# 4.net
KiCad netlist of a schematic drawn in Altium Designer
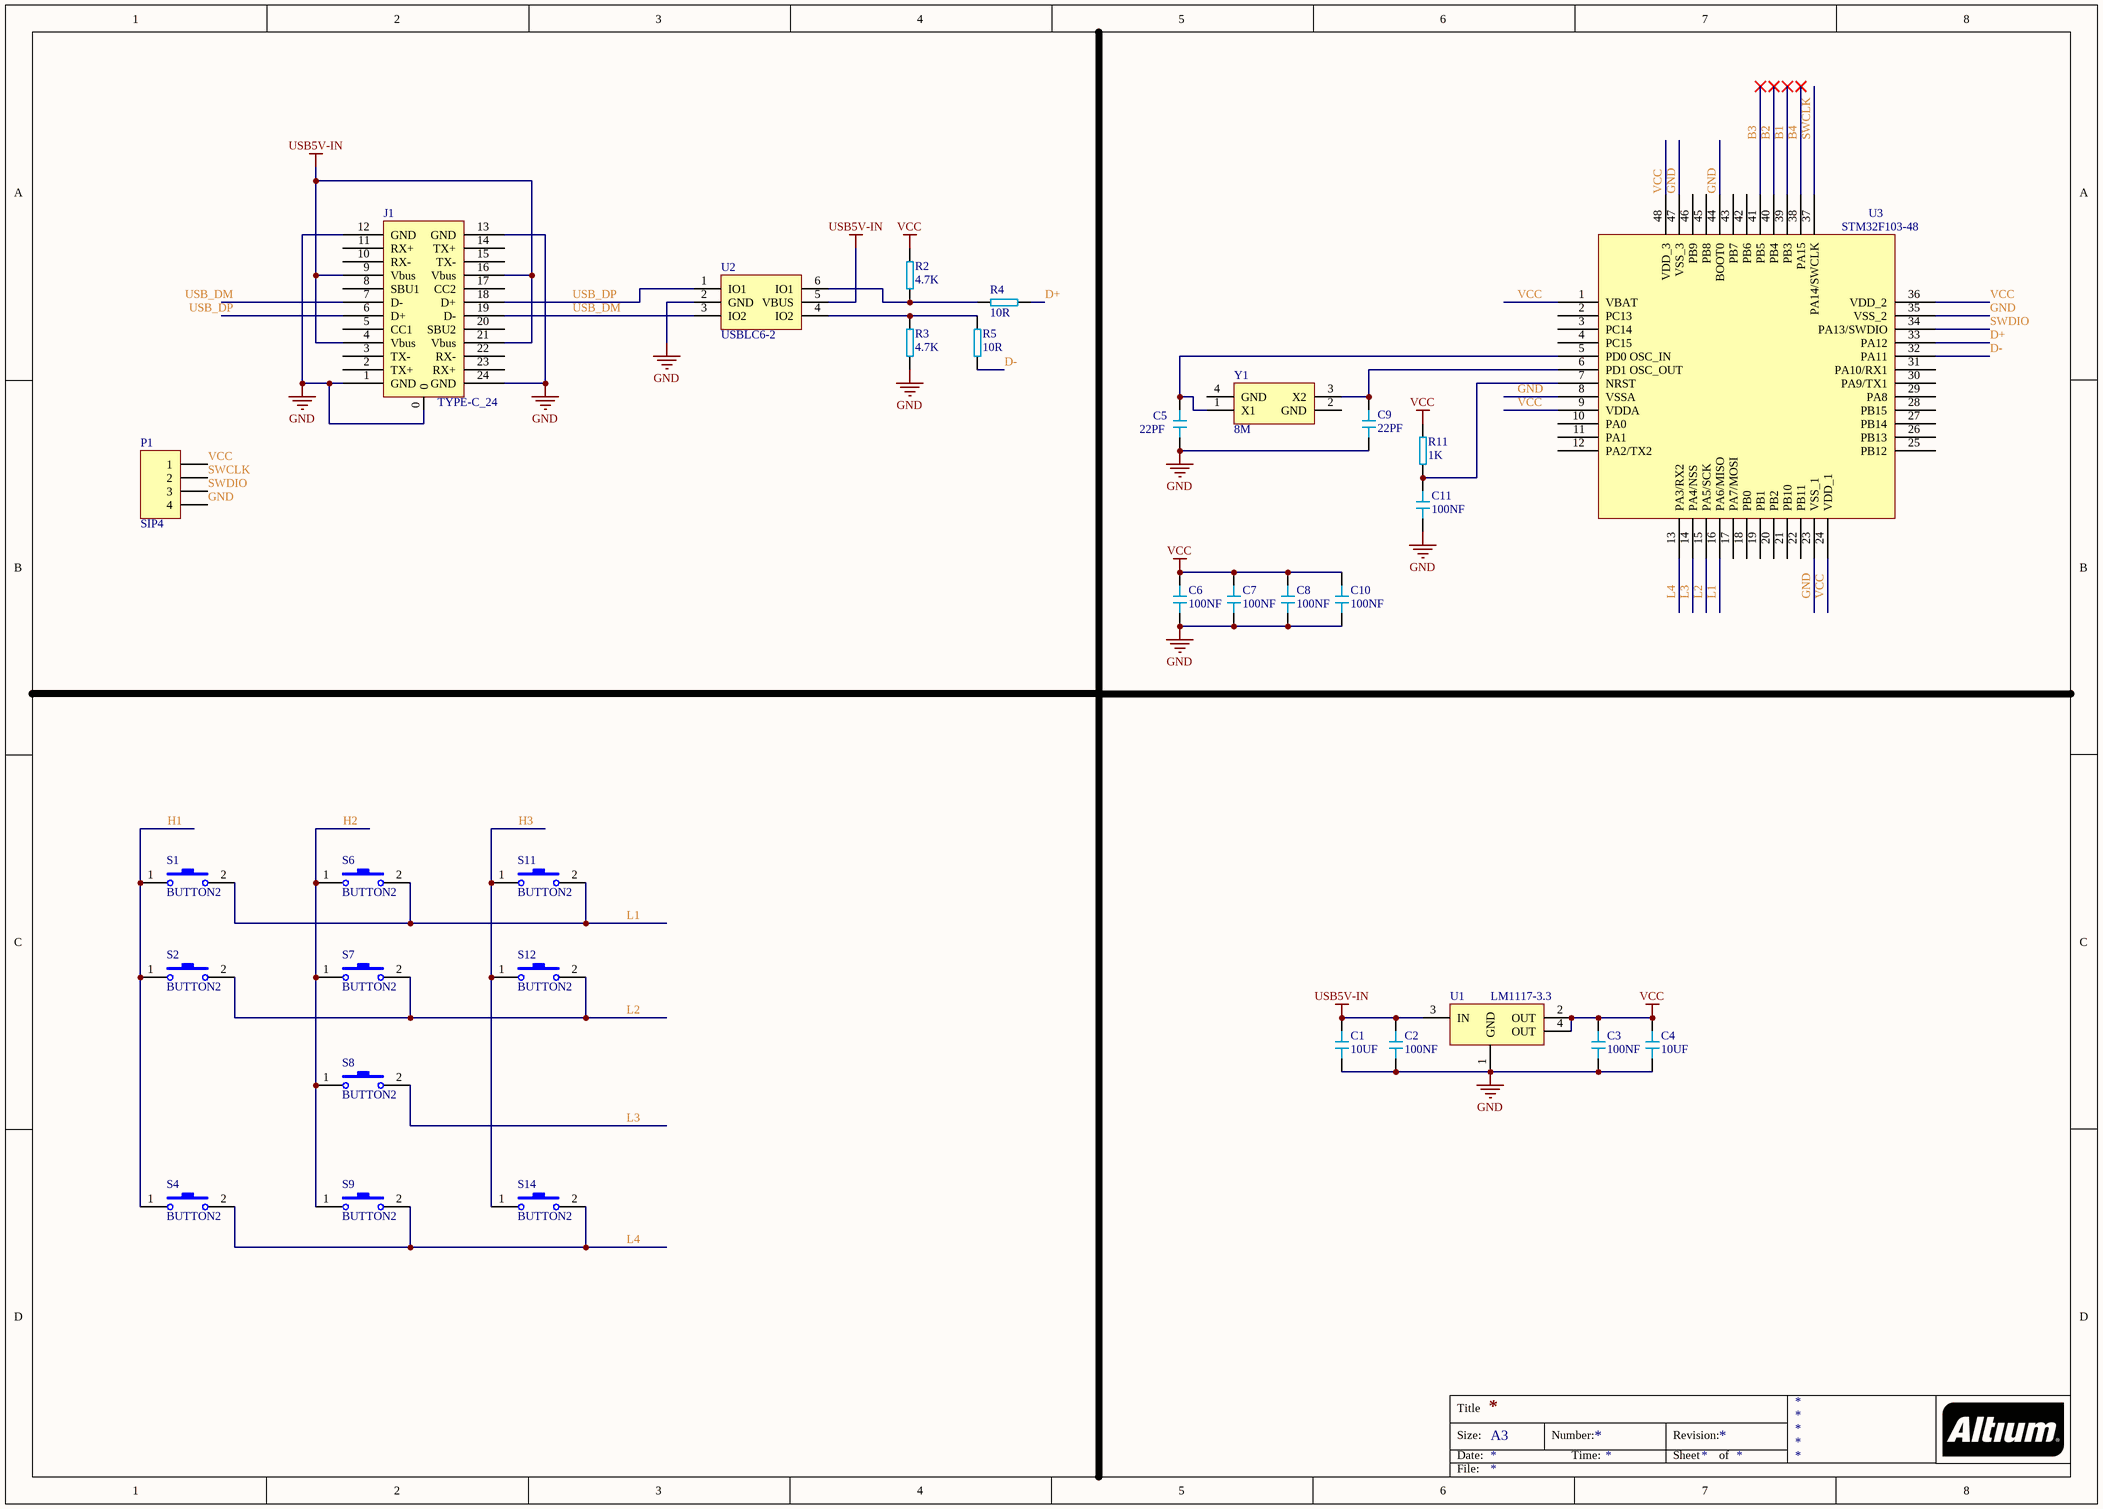
[diagram p0: 练习4原理图.SchDoc]

(export (version "E")
  (design (tool "Eeschema 10.0.6"))
  (components
    (comp (ref "C1")
      (value "10UF")
      (footprint "C0603")
      (description "贴片电容")
      (libsource (lib "base") (part "C0603"))
    )
    (comp (ref "C2")
      (value "100NF")
      (footprint "C0603")
      (description "贴片电容")
      (libsource (lib "base") (part "C0603"))
    )
    (comp (ref "C3")
      (value "100NF")
      (footprint "C0603")
      (description "贴片电容")
      (libsource (lib "base") (part "C0603"))
    )
    (comp (ref "C4")
      (value "10UF")
      (footprint "C0603")
      (description "贴片电容")
      (libsource (lib "base") (part "C0603"))
    )
    (comp (ref "C5")
      (value "22PF")
      (footprint "C0603")
      (description "贴片电容")
      (libsource (lib "base") (part "C0603"))
    )
    (comp (ref "C6")
      (value "100NF")
      (footprint "C0603")
      (description "贴片电容")
      (libsource (lib "base") (part "C0603"))
    )
    (comp (ref "C7")
      (value "100NF")
      (footprint "C0603")
      (description "贴片电容")
      (libsource (lib "base") (part "C0603"))
    )
    (comp (ref "C8")
      (value "100NF")
      (footprint "C0603")
      (description "贴片电容")
      (libsource (lib "base") (part "C0603"))
    )
    (comp (ref "C9")
      (value "22PF")
      (footprint "C0603")
      (description "贴片电容")
      (libsource (lib "base") (part "C0603"))
    )
    (comp (ref "C10")
      (value "100NF")
      (footprint "C0603")
      (description "贴片电容")
      (libsource (lib "base") (part "C0603"))
    )
    (comp (ref "C11")
      (value "100NF")
      (footprint "C0603")
      (description "贴片电容")
      (libsource (lib "base") (part "C0603"))
    )
    (comp (ref "J1")
      (value "TYPE-C_24")
      (footprint "TYPE-C24P")
      (libsource (lib "Schlib_pok") (part "TYPE-C_24"))
    )
    (comp (ref "P1")
      (value "SIP4")
      (footprint "SIP4")
      (description "连接器")
      (fields (field (name "PUBLISHER") "Altium Limited"))
      (libsource (lib "base") (part "SIP4"))
    )
    (comp (ref "R2")
      (value "4.7K")
      (footprint "R0603")
      (description "贴片电阻")
      (libsource (lib "base") (part "R-0603"))
    )
    (comp (ref "R3")
      (value "4.7K")
      (footprint "R0603")
      (description "贴片电阻")
      (libsource (lib "base") (part "R-0603"))
    )
    (comp (ref "R4")
      (value "10R")
      (footprint "R0603")
      (description "贴片电阻")
      (libsource (lib "base") (part "R-0603"))
    )
    (comp (ref "R5")
      (value "10R")
      (footprint "R0603")
      (description "贴片电阻")
      (libsource (lib "base") (part "R-0603"))
    )
    (comp (ref "R11")
      (value "1K")
      (footprint "R0603")
      (description "贴片电阻")
      (libsource (lib "base") (part "R-0603"))
    )
    (comp (ref "S1")
      (value "BUTTON2")
      (footprint "KEY")
      (description "按钮")
      (fields (field (name "PUBLISHER") "Altium Limited"))
      (libsource (lib "base") (part "BUTTON2"))
    )
    (comp (ref "S2")
      (value "BUTTON2")
      (footprint "KEY")
      (description "按钮")
      (fields (field (name "PUBLISHER") "Altium Limited"))
      (libsource (lib "base") (part "BUTTON2"))
    )
    (comp (ref "S4")
      (value "BUTTON2")
      (footprint "KEY")
      (description "按钮")
      (fields (field (name "PUBLISHER") "Altium Limited"))
      (libsource (lib "base") (part "BUTTON2"))
    )
    (comp (ref "S6")
      (value "BUTTON2")
      (footprint "KEY")
      (description "按钮")
      (fields (field (name "PUBLISHER") "Altium Limited"))
      (libsource (lib "base") (part "BUTTON2"))
    )
    (comp (ref "S7")
      (value "BUTTON2")
      (footprint "KEY")
      (description "按钮")
      (fields (field (name "PUBLISHER") "Altium Limited"))
      (libsource (lib "base") (part "BUTTON2"))
    )
    (comp (ref "S8")
      (value "BUTTON2")
      (footprint "KEY")
      (description "按钮")
      (fields (field (name "PUBLISHER") "Altium Limited"))
      (libsource (lib "base") (part "BUTTON2"))
    )
    (comp (ref "S9")
      (value "BUTTON2")
      (footprint "KEY")
      (description "按钮")
      (fields (field (name "PUBLISHER") "Altium Limited"))
      (libsource (lib "base") (part "BUTTON2"))
    )
    (comp (ref "S11")
      (value "BUTTON2")
      (footprint "KEY")
      (description "按钮")
      (fields (field (name "PUBLISHER") "Altium Limited"))
      (libsource (lib "base") (part "BUTTON2"))
    )
    (comp (ref "S12")
      (value "BUTTON2")
      (footprint "KEY")
      (description "按钮")
      (fields (field (name "PUBLISHER") "Altium Limited"))
      (libsource (lib "base") (part "BUTTON2"))
    )
    (comp (ref "S14")
      (value "BUTTON2")
      (footprint "KEY")
      (description "按钮")
      (fields (field (name "PUBLISHER") "Altium Limited"))
      (libsource (lib "base") (part "BUTTON2"))
    )
    (comp (ref "U1")
      (value "LM1117-3.3")
      (footprint "SOT223")
      (description "芯片")
      (fields (field (name "PUBLISHER") "Altium Limited"))
      (libsource (lib "base") (part "1117"))
    )
    (comp (ref "U2") (value "USBLC6-2") (footprint "SOT23-6") (libsource (lib "Chip") (part "USBLC6-2")))
    (comp (ref "U3")
      (value "STM32F103-48")
      (footprint "LQFP48")
      (libsource (lib "Chip") (part "STM32F103-48"))
    )
    (comp (ref "Y1")
      (value "8M")
      (footprint "XTAL-3225-4")
      (description "无源晶振")
      (fields (field (name "PUBLISHER") "Altium Limited"))
      (libsource (lib "base") (part "XTAL-4-W"))
    )
  )
  (nets
    (net (code "1") (name "/B1") (class "Default")
      (node (ref "U3") (pin "39") (pinfunction "PB3_39") (pintype "passive+no_connect"))
    )
    (net (code "2") (name "/B2") (class "Default")
      (node (ref "U3") (pin "40") (pinfunction "PB4_40") (pintype "passive+no_connect"))
    )
    (net (code "3") (name "/B3") (class "Default")
      (node (ref "U3") (pin "41") (pinfunction "PB5_41") (pintype "passive+no_connect"))
    )
    (net (code "4") (name "/B4") (class "Default")
      (node (ref "U3") (pin "38") (pinfunction "PA15_38") (pintype "passive+no_connect"))
    )
    (net (code "5") (name "/D+") (class "Default")
      (node (ref "R4") (pin "2") (pinfunction "2_2") (pintype "passive"))
      (node (ref "U3") (pin "33") (pinfunction "PA12_33") (pintype "passive"))
    )
    (net (code "6") (name "/D-") (class "Default")
      (node (ref "R5") (pin "1") (pinfunction "1_1") (pintype "passive"))
      (node (ref "U3") (pin "32") (pinfunction "PA11_32") (pintype "passive"))
    )
    (net (code "7") (name "/H1") (class "Default")
      (node (ref "S1") (pin "1") (pinfunction "1_1") (pintype "passive"))
      (node (ref "S2") (pin "1") (pinfunction "1_1") (pintype "passive"))
      (node (ref "S4") (pin "1") (pinfunction "1_1") (pintype "passive"))
    )
    (net (code "8") (name "/H2") (class "Default")
      (node (ref "S6") (pin "1") (pinfunction "1_1") (pintype "passive"))
      (node (ref "S7") (pin "1") (pinfunction "1_1") (pintype "passive"))
      (node (ref "S8") (pin "1") (pinfunction "1_1") (pintype "passive"))
      (node (ref "S9") (pin "1") (pinfunction "1_1") (pintype "passive"))
    )
    (net (code "9") (name "/H3") (class "Default")
      (node (ref "S11") (pin "1") (pinfunction "1_1") (pintype "passive"))
      (node (ref "S12") (pin "1") (pinfunction "1_1") (pintype "passive"))
      (node (ref "S14") (pin "1") (pinfunction "1_1") (pintype "passive"))
    )
    (net (code "10") (name "/L1") (class "Default")
      (node (ref "S1") (pin "2") (pinfunction "2_2") (pintype "passive"))
      (node (ref "S11") (pin "2") (pinfunction "2_2") (pintype "passive"))
      (node (ref "S6") (pin "2") (pinfunction "2_2") (pintype "passive"))
      (node (ref "U3") (pin "16") (pinfunction "PA6/MISO_16") (pintype "passive"))
    )
    (net (code "11") (name "/L2") (class "Default")
      (node (ref "S12") (pin "2") (pinfunction "2_2") (pintype "passive"))
      (node (ref "S2") (pin "2") (pinfunction "2_2") (pintype "passive"))
      (node (ref "S7") (pin "2") (pinfunction "2_2") (pintype "passive"))
      (node (ref "U3") (pin "15") (pinfunction "PA5/SCK_15") (pintype "passive"))
    )
    (net (code "12") (name "/L3") (class "Default")
      (node (ref "S8") (pin "2") (pinfunction "2_2") (pintype "passive"))
      (node (ref "U3") (pin "14") (pinfunction "PA4/NSS_14") (pintype "passive"))
    )
    (net (code "13") (name "/L4") (class "Default")
      (node (ref "S14") (pin "2") (pinfunction "2_2") (pintype "passive"))
      (node (ref "S4") (pin "2") (pinfunction "2_2") (pintype "passive"))
      (node (ref "S9") (pin "2") (pinfunction "2_2") (pintype "passive"))
      (node (ref "U3") (pin "13") (pinfunction "PA3/RX2_13") (pintype "passive"))
    )
    (net (code "14") (name "/SWCLK") (class "Default")
      (node (ref "P1") (pin "2") (pinfunction "2_2") (pintype "passive"))
      (node (ref "U3") (pin "37") (pinfunction "PA14/SWCLK_37") (pintype "passive"))
    )
    (net (code "15") (name "/SWDIO") (class "Default")
      (node (ref "P1") (pin "3") (pinfunction "3_3") (pintype "passive"))
      (node (ref "U3") (pin "34") (pinfunction "PA13/SWDIO_34") (pintype "passive"))
    )
    (net (code "16") (name "/USB_DM") (class "Default")
      (node (ref "J1") (pin "19") (pinfunction "D-_19") (pintype "passive"))
      (node (ref "J1") (pin "7") (pinfunction "D-_7") (pintype "passive"))
      (node (ref "U2") (pin "3") (pinfunction "IO2_3") (pintype "passive"))
    )
    (net (code "17") (name "/USB_DP") (class "Default")
      (node (ref "J1") (pin "18") (pinfunction "D+_18") (pintype "passive"))
      (node (ref "J1") (pin "6") (pinfunction "D+_6") (pintype "passive"))
      (node (ref "U2") (pin "1") (pinfunction "IO1_1") (pintype "passive"))
    )
    (net (code "18") (name "GND") (class "Default")
      (node (ref "C1") (pin "1") (pinfunction "1_1") (pintype "passive"))
      (node (ref "C10") (pin "1") (pinfunction "1_1") (pintype "passive"))
      (node (ref "C11") (pin "1") (pinfunction "1_1") (pintype "passive"))
      (node (ref "C2") (pin "1") (pinfunction "1_1") (pintype "passive"))
      (node (ref "C3") (pin "1") (pinfunction "1_1") (pintype "passive"))
      (node (ref "C4") (pin "1") (pinfunction "1_1") (pintype "passive"))
      (node (ref "C5") (pin "1") (pinfunction "1_1") (pintype "passive"))
      (node (ref "C6") (pin "1") (pinfunction "1_1") (pintype "passive"))
      (node (ref "C7") (pin "1") (pinfunction "1_1") (pintype "passive"))
      (node (ref "C8") (pin "1") (pinfunction "1_1") (pintype "passive"))
      (node (ref "C9") (pin "1") (pinfunction "1_1") (pintype "passive"))
      (node (ref "J1") (pin "0") (pinfunction "0_0") (pintype "passive"))
      (node (ref "J1") (pin "1") (pinfunction "GND_1") (pintype "passive"))
      (node (ref "J1") (pin "12") (pinfunction "GND_12") (pintype "passive"))
      (node (ref "J1") (pin "13") (pinfunction "GND_13") (pintype "passive"))
      (node (ref "J1") (pin "24") (pinfunction "GND_24") (pintype "passive"))
      (node (ref "P1") (pin "4") (pinfunction "4_4") (pintype "passive"))
      (node (ref "R3") (pin "1") (pinfunction "1_1") (pintype "passive"))
      (node (ref "U1") (pin "1") (pinfunction "GND_1") (pintype "passive"))
      (node (ref "U2") (pin "2") (pinfunction "GND_2") (pintype "passive"))
      (node (ref "U3") (pin "23") (pinfunction "VSS_1_23") (pintype "passive"))
      (node (ref "U3") (pin "35") (pinfunction "VSS_2_35") (pintype "passive"))
      (node (ref "U3") (pin "44") (pinfunction "BOOT0_44") (pintype "passive"))
      (node (ref "U3") (pin "47") (pinfunction "VSS_3_47") (pintype "passive"))
      (node (ref "U3") (pin "8") (pinfunction "VSSA_8") (pintype "passive"))
    )
    (net (code "19") (name "Net-(R2-Pad1)") (class "Default")
      (node (ref "R2") (pin "1") (pinfunction "1_1") (pintype "passive"))
      (node (ref "R4") (pin "1") (pinfunction "1_1") (pintype "passive"))
      (node (ref "U2") (pin "6") (pinfunction "IO1_6") (pintype "passive"))
    )
    (net (code "20") (name "Net-(R3-Pad2)") (class "Default")
      (node (ref "R3") (pin "2") (pinfunction "2_2") (pintype "passive"))
      (node (ref "R5") (pin "2") (pinfunction "2_2") (pintype "passive"))
      (node (ref "U2") (pin "4") (pinfunction "IO2_4") (pintype "passive"))
    )
    (net (code "21") (name "Net-(U3-NRST)") (class "Default")
      (node (ref "C11") (pin "2") (pinfunction "2_2") (pintype "passive"))
      (node (ref "R11") (pin "1") (pinfunction "1_1") (pintype "passive"))
      (node (ref "U3") (pin "7") (pinfunction "NRST_7") (pintype "passive"))
    )
    (net (code "22") (name "Net-(U3-PD0_OSC_IN)") (class "Default")
      (node (ref "C5") (pin "2") (pinfunction "2_2") (pintype "passive"))
      (node (ref "U3") (pin "5") (pinfunction "PD0_OSC_IN_5") (pintype "passive"))
      (node (ref "Y1") (pin "1") (pinfunction "X1_1") (pintype "passive"))
    )
    (net (code "23") (name "Net-(U3-PD1_OSC_OUT)") (class "Default")
      (node (ref "C9") (pin "2") (pinfunction "2_2") (pintype "passive"))
      (node (ref "U3") (pin "6") (pinfunction "PD1_OSC_OUT_6") (pintype "passive"))
      (node (ref "Y1") (pin "3") (pinfunction "X2_3") (pintype "passive"))
    )
    (net (code "24") (name "USB5V-IN") (class "Default")
      (node (ref "C1") (pin "2") (pinfunction "2_2") (pintype "passive"))
      (node (ref "C2") (pin "2") (pinfunction "2_2") (pintype "passive"))
      (node (ref "J1") (pin "16") (pinfunction "Vbus_16") (pintype "passive"))
      (node (ref "J1") (pin "21") (pinfunction "Vbus_21") (pintype "passive"))
      (node (ref "J1") (pin "4") (pinfunction "Vbus_4") (pintype "passive"))
      (node (ref "J1") (pin "9") (pinfunction "Vbus_9") (pintype "passive"))
      (node (ref "U1") (pin "3") (pinfunction "IN_3") (pintype "passive"))
      (node (ref "U2") (pin "5") (pinfunction "VBUS_5") (pintype "passive"))
    )
    (net (code "25") (name "VCC") (class "Default")
      (node (ref "C10") (pin "2") (pinfunction "2_2") (pintype "passive"))
      (node (ref "C3") (pin "2") (pinfunction "2_2") (pintype "passive"))
      (node (ref "C4") (pin "2") (pinfunction "2_2") (pintype "passive"))
      (node (ref "C6") (pin "2") (pinfunction "2_2") (pintype "passive"))
      (node (ref "C7") (pin "2") (pinfunction "2_2") (pintype "passive"))
      (node (ref "C8") (pin "2") (pinfunction "2_2") (pintype "passive"))
      (node (ref "P1") (pin "1") (pinfunction "1_1") (pintype "passive"))
      (node (ref "R11") (pin "2") (pinfunction "2_2") (pintype "passive"))
      (node (ref "R2") (pin "2") (pinfunction "2_2") (pintype "passive"))
      (node (ref "U1") (pin "2") (pinfunction "OUT_2") (pintype "passive"))
      (node (ref "U1") (pin "4") (pinfunction "OUT_4") (pintype "passive"))
      (node (ref "U3") (pin "1") (pinfunction "VBAT_1") (pintype "passive"))
      (node (ref "U3") (pin "24") (pinfunction "VDD_1_24") (pintype "passive"))
      (node (ref "U3") (pin "36") (pinfunction "VDD_2_36") (pintype "passive"))
      (node (ref "U3") (pin "48") (pinfunction "VDD_3_48") (pintype "passive"))
      (node (ref "U3") (pin "9") (pinfunction "VDDA_9") (pintype "passive"))
    )
    (net (code "26") (name "unconnected-(J1-CC1-Pad5)") (class "Default")
      (node (ref "J1") (pin "5") (pinfunction "CC1_5") (pintype "passive"))
    )
    (net (code "27") (name "unconnected-(J1-CC2-Pad17)") (class "Default")
      (node (ref "J1") (pin "17") (pinfunction "CC2_17") (pintype "passive"))
    )
    (net (code "28") (name "unconnected-(J1-RX+-Pad11)") (class "Default")
      (node (ref "J1") (pin "11") (pinfunction "RX+_11") (pintype "passive"))
    )
    (net (code "29") (name "unconnected-(J1-RX+-Pad23)") (class "Default")
      (node (ref "J1") (pin "23") (pinfunction "RX+_23") (pintype "passive"))
    )
    (net (code "30") (name "unconnected-(J1-RX--Pad10)") (class "Default")
      (node (ref "J1") (pin "10") (pinfunction "RX-_10") (pintype "passive"))
    )
    (net (code "31") (name "unconnected-(J1-RX--Pad22)") (class "Default")
      (node (ref "J1") (pin "22") (pinfunction "RX-_22") (pintype "passive"))
    )
    (net (code "32") (name "unconnected-(J1-SBU1-Pad8)") (class "Default")
      (node (ref "J1") (pin "8") (pinfunction "SBU1_8") (pintype "passive"))
    )
    (net (code "33") (name "unconnected-(J1-SBU2-Pad20)") (class "Default")
      (node (ref "J1") (pin "20") (pinfunction "SBU2_20") (pintype "passive"))
    )
    (net (code "34") (name "unconnected-(J1-TX+-Pad2)") (class "Default")
      (node (ref "J1") (pin "2") (pinfunction "TX+_2") (pintype "passive"))
    )
    (net (code "35") (name "unconnected-(J1-TX+-Pad14)") (class "Default")
      (node (ref "J1") (pin "14") (pinfunction "TX+_14") (pintype "passive"))
    )
    (net (code "36") (name "unconnected-(J1-TX--Pad3)") (class "Default")
      (node (ref "J1") (pin "3") (pinfunction "TX-_3") (pintype "passive"))
    )
    (net (code "37") (name "unconnected-(J1-TX--Pad15)") (class "Default")
      (node (ref "J1") (pin "15") (pinfunction "TX-_15") (pintype "passive"))
    )
    (net (code "38") (name "unconnected-(U3-PA0-Pad10)") (class "Default")
      (node (ref "U3") (pin "10") (pinfunction "PA0_10") (pintype "passive"))
    )
    (net (code "39") (name "unconnected-(U3-PA1-Pad11)") (class "Default")
      (node (ref "U3") (pin "11") (pinfunction "PA1_11") (pintype "passive"))
    )
    (net (code "40") (name "unconnected-(U3-PA2{slash}TX2-Pad12)") (class "Default")
      (node (ref "U3") (pin "12") (pinfunction "PA2/TX2_12") (pintype "passive"))
    )
    (net (code "41") (name "unconnected-(U3-PA7{slash}MOSI-Pad17)") (class "Default")
      (node (ref "U3") (pin "17") (pinfunction "PA7/MOSI_17") (pintype "passive"))
    )
    (net (code "42") (name "unconnected-(U3-PA8-Pad29)") (class "Default")
      (node (ref "U3") (pin "29") (pinfunction "PA8_29") (pintype "passive"))
    )
    (net (code "43") (name "unconnected-(U3-PA9{slash}TX1-Pad30)") (class "Default")
      (node (ref "U3") (pin "30") (pinfunction "PA9/TX1_30") (pintype "passive"))
    )
    (net (code "44") (name "unconnected-(U3-PA10{slash}RX1-Pad31)") (class "Default")
      (node (ref "U3") (pin "31") (pinfunction "PA10/RX1_31") (pintype "passive"))
    )
    (net (code "45") (name "unconnected-(U3-PB0-Pad18)") (class "Default")
      (node (ref "U3") (pin "18") (pinfunction "PB0_18") (pintype "passive"))
    )
    (net (code "46") (name "unconnected-(U3-PB1-Pad19)") (class "Default")
      (node (ref "U3") (pin "19") (pinfunction "PB1_19") (pintype "passive"))
    )
    (net (code "47") (name "unconnected-(U3-PB2-Pad20)") (class "Default")
      (node (ref "U3") (pin "20") (pinfunction "PB2_20") (pintype "passive"))
    )
    (net (code "48") (name "unconnected-(U3-PB6-Pad42)") (class "Default")
      (node (ref "U3") (pin "42") (pinfunction "PB6_42") (pintype "passive"))
    )
    (net (code "49") (name "unconnected-(U3-PB7-Pad43)") (class "Default")
      (node (ref "U3") (pin "43") (pinfunction "PB7_43") (pintype "passive"))
    )
    (net (code "50") (name "unconnected-(U3-PB8-Pad45)") (class "Default")
      (node (ref "U3") (pin "45") (pinfunction "PB8_45") (pintype "passive"))
    )
    (net (code "51") (name "unconnected-(U3-PB9-Pad46)") (class "Default")
      (node (ref "U3") (pin "46") (pinfunction "PB9_46") (pintype "passive"))
    )
    (net (code "52") (name "unconnected-(U3-PB10-Pad21)") (class "Default")
      (node (ref "U3") (pin "21") (pinfunction "PB10_21") (pintype "passive"))
    )
    (net (code "53") (name "unconnected-(U3-PB11-Pad22)") (class "Default")
      (node (ref "U3") (pin "22") (pinfunction "PB11_22") (pintype "passive"))
    )
    (net (code "54") (name "unconnected-(U3-PB12-Pad25)") (class "Default")
      (node (ref "U3") (pin "25") (pinfunction "PB12_25") (pintype "passive"))
    )
    (net (code "55") (name "unconnected-(U3-PB13-Pad26)") (class "Default")
      (node (ref "U3") (pin "26") (pinfunction "PB13_26") (pintype "passive"))
    )
    (net (code "56") (name "unconnected-(U3-PB14-Pad27)") (class "Default")
      (node (ref "U3") (pin "27") (pinfunction "PB14_27") (pintype "passive"))
    )
    (net (code "57") (name "unconnected-(U3-PB15-Pad28)") (class "Default")
      (node (ref "U3") (pin "28") (pinfunction "PB15_28") (pintype "passive"))
    )
    (net (code "58") (name "unconnected-(U3-PC13-Pad2)") (class "Default")
      (node (ref "U3") (pin "2") (pinfunction "PC13_2") (pintype "passive"))
    )
    (net (code "59") (name "unconnected-(U3-PC14-Pad3)") (class "Default")
      (node (ref "U3") (pin "3") (pinfunction "PC14_3") (pintype "passive"))
    )
    (net (code "60") (name "unconnected-(U3-PC15-Pad4)") (class "Default")
      (node (ref "U3") (pin "4") (pinfunction "PC15_4") (pintype "passive"))
    )
    (net (code "61") (name "unconnected-(Y1-GND-Pad2)") (class "Default")
      (node (ref "Y1") (pin "2") (pinfunction "GND_2") (pintype "passive"))
    )
    (net (code "62") (name "unconnected-(Y1-GND-Pad4)") (class "Default")
      (node (ref "Y1") (pin "4") (pinfunction "GND_4") (pintype "passive"))
    )
  )
)
